# XForm_Clang.net
KiCad netlist of a schematic drawn in EAGLE
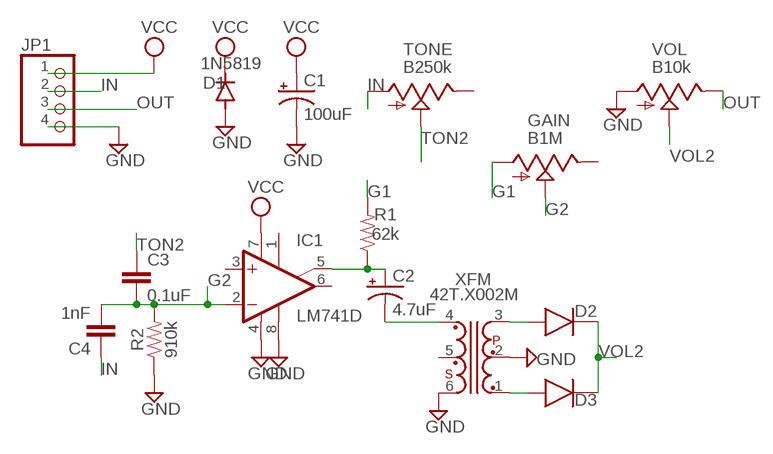
[diagram p0: schematic, sheet 1]

(export (version "E")
  (design (tool "Eeschema 10.0.6"))
  (components
    (comp (ref "C1")
      (value "100uF")
      (footprint "eagle-import:PAN_B_SMD+THRU")
      (libsource (lib "eagle-import") (part "CAP_SMD+THRUPAN_B"))
    )
    (comp (ref "C2")
      (value "4.7uF")
      (footprint "eagle-import:PAN_B_SMD+THRU")
      (libsource (lib "eagle-import") (part "CAP_SMD+THRUPAN_B"))
    )
    (comp (ref "C3")
      (value "0.1uF")
      (footprint "eagle-import:0603")
      (libsource (lib "eagle-import") (part "0.1UF-0603-25V-(+80/-20%)"))
    )
    (comp (ref "C4")
      (value "1nF")
      (footprint "eagle-import:0603")
      (libsource (lib "eagle-import") (part "1.0NF/1000PF-0603-50V-10%"))
    )
    (comp (ref "D1")
      (value "1N5819")
      (footprint "eagle-import:SOD123")
      (libsource (lib "eagle-import") (part "DIODE-SOD123"))
    )
    (comp (ref "D2")
      (value "1N4148")
      (footprint "eagle-import:D35-10")
      (libsource (lib "eagle-import") (part "1N4148"))
    )
    (comp (ref "D3")
      (value "1N4148")
      (footprint "eagle-import:D35-10")
      (libsource (lib "eagle-import") (part "1N4148"))
    )
    (comp (ref "GAIN")
      (value "B1M")
      (footprint "eagle-import:9MM_SNAP-IN_POT")
      (libsource (lib "eagle-import") (part "9MM_SNAP-IN_POT_"))
    )
    (comp (ref "IC1")
      (value "LM741D")
      (footprint "eagle-import:SO08")
      (libsource (lib "eagle-import") (part "741DLM"))
    )
    (comp (ref "JP1")
      (value "PINHD-1X4")
      (footprint "eagle-import:1X04")
      (libsource (lib "eagle-import") (part "PINHD-1X4"))
    )
    (comp (ref "R1")
      (value "62k")
      (footprint "eagle-import:0603")
      (libsource (lib "eagle-import") (part "62KOHM-0603-1/10W-5%"))
    )
    (comp (ref "R2")
      (value "910k")
      (footprint "eagle-import:0603")
      (libsource (lib "eagle-import") (part "820KOHM-0603-1/10W-1%"))
    )
    (comp (ref "TONE")
      (value "B250k")
      (footprint "eagle-import:9MM_SNAP-IN_POT")
      (libsource (lib "eagle-import") (part "9MM_SNAP-IN_POT_"))
    )
    (comp (ref "VOL")
      (value "B10k")
      (footprint "eagle-import:9MM_SNAP-IN_POT")
      (libsource (lib "eagle-import") (part "9MM_SNAP-IN_POT_"))
    )
    (comp (ref "XFM")
      (value "42T.X002M")
      (footprint "eagle-import:42TM")
      (libsource (lib "eagle-import") (part "42T.XM002"))
    )
  )
  (nets
    (net (code "1") (name "/G1") (class "Default")
      (node (ref "GAIN") (pin "1") (pinfunction "A_1") (pintype "passive"))
      (node (ref "R1") (pin "2") (pinfunction "2_2") (pintype "passive"))
    )
    (net (code "2") (name "/G2") (class "Default")
      (node (ref "C3") (pin "2") (pinfunction "2_2") (pintype "passive"))
      (node (ref "C4") (pin "2") (pinfunction "2_2") (pintype "passive"))
      (node (ref "GAIN") (pin "2") (pinfunction "S_2") (pintype "passive"))
      (node (ref "IC1") (pin "2") (pinfunction "-IN_2") (pintype "input"))
      (node (ref "R2") (pin "2") (pinfunction "2_2") (pintype "passive"))
    )
    (net (code "3") (name "/IN") (class "Default")
      (node (ref "C4") (pin "1") (pinfunction "1_1") (pintype "passive"))
      (node (ref "JP1") (pin "2") (pinfunction "2_2") (pintype "passive"))
      (node (ref "TONE") (pin "1") (pinfunction "A_1") (pintype "passive"))
    )
    (net (code "4") (name "/OUT") (class "Default")
      (node (ref "JP1") (pin "3") (pinfunction "3_3") (pintype "passive"))
      (node (ref "VOL") (pin "3") (pinfunction "E_3") (pintype "passive"))
    )
    (net (code "5") (name "/TON2") (class "Default")
      (node (ref "C3") (pin "1") (pinfunction "1_1") (pintype "passive"))
      (node (ref "TONE") (pin "2") (pinfunction "S_2") (pintype "passive"))
    )
    (net (code "6") (name "/VOL2") (class "Default")
      (node (ref "D2") (pin "K") (pinfunction "K_K") (pintype "passive"))
      (node (ref "D3") (pin "K") (pinfunction "K_K") (pintype "passive"))
      (node (ref "VOL") (pin "2") (pinfunction "S_2") (pintype "passive"))
    )
    (net (code "7") (name "GND") (class "Default")
      (node (ref "C1") (pin "-") (pinfunction "-_-") (pintype "passive"))
      (node (ref "C1") (pin "--") (pinfunction "-_--") (pintype "passive"))
      (node (ref "D1") (pin "A") (pinfunction "A_A") (pintype "passive"))
      (node (ref "IC1") (pin "4") (pinfunction "V-_4") (pintype "power_in"))
      (node (ref "IC1") (pin "8") (pinfunction "OPT_8") (pintype "passive"))
      (node (ref "JP1") (pin "4") (pinfunction "4_4") (pintype "passive"))
      (node (ref "R2") (pin "1") (pinfunction "1_1") (pintype "passive"))
      (node (ref "VOL") (pin "1") (pinfunction "A_1") (pintype "passive"))
      (node (ref "XFM") (pin "2") (pinfunction "2_2") (pintype "passive"))
      (node (ref "XFM") (pin "6") (pinfunction "6_6") (pintype "passive"))
    )
    (net (code "8") (name "Net-(C2---Pad--)") (class "Default")
      (node (ref "C2") (pin "-") (pinfunction "-_-") (pintype "passive"))
      (node (ref "C2") (pin "--") (pinfunction "-_--") (pintype "passive"))
      (node (ref "XFM") (pin "4") (pinfunction "4_4") (pintype "passive"))
    )
    (net (code "9") (name "Net-(D2-PadA)") (class "Default")
      (node (ref "D2") (pin "A") (pinfunction "A_A") (pintype "passive"))
      (node (ref "XFM") (pin "3") (pinfunction "3_3") (pintype "passive"))
    )
    (net (code "10") (name "Net-(D3-PadA)") (class "Default")
      (node (ref "D3") (pin "A") (pinfunction "A_A") (pintype "passive"))
      (node (ref "XFM") (pin "1") (pinfunction "1_1") (pintype "passive"))
    )
    (net (code "11") (name "Net-(IC1-ON2)") (class "Default")
      (node (ref "C2") (pin "+") (pinfunction "+_+") (pintype "passive"))
      (node (ref "C2") (pin "++") (pinfunction "+_++") (pintype "passive"))
      (node (ref "IC1") (pin "5") (pinfunction "ON2_5") (pintype "passive"))
      (node (ref "R1") (pin "1") (pinfunction "1_1") (pintype "passive"))
    )
    (net (code "12") (name "VCC") (class "Default")
      (node (ref "C1") (pin "+") (pinfunction "+_+") (pintype "passive"))
      (node (ref "C1") (pin "++") (pinfunction "+_++") (pintype "passive"))
      (node (ref "D1") (pin "C") (pinfunction "C_C") (pintype "passive"))
      (node (ref "IC1") (pin "7") (pinfunction "V+_7") (pintype "power_in"))
      (node (ref "JP1") (pin "1") (pinfunction "1_1") (pintype "passive"))
    )
    (net (code "13") (name "unconnected-(GAIN-E-Pad3)") (class "Default")
      (node (ref "GAIN") (pin "3") (pinfunction "E_3") (pintype "passive"))
    )
    (net (code "14") (name "unconnected-(IC1-+IN-Pad3)") (class "Default")
      (node (ref "IC1") (pin "3") (pinfunction "+IN_3") (pintype "input"))
    )
    (net (code "15") (name "unconnected-(IC1-ON1-Pad1)") (class "Default")
      (node (ref "IC1") (pin "1") (pinfunction "ON1_1") (pintype "passive"))
    )
    (net (code "16") (name "unconnected-(IC1-OUT-Pad6)") (class "Default")
      (node (ref "IC1") (pin "6") (pinfunction "OUT_6") (pintype "output"))
    )
    (net (code "17") (name "unconnected-(TONE-E-Pad3)") (class "Default")
      (node (ref "TONE") (pin "3") (pinfunction "E_3") (pintype "passive"))
    )
    (net (code "18") (name "unconnected-(XFM-Pad5)") (class "Default")
      (node (ref "XFM") (pin "5") (pinfunction "5_5") (pintype "passive"))
    )
  )
)
